# Outputs.net
KiCad netlist of a schematic drawn in Altium Designer
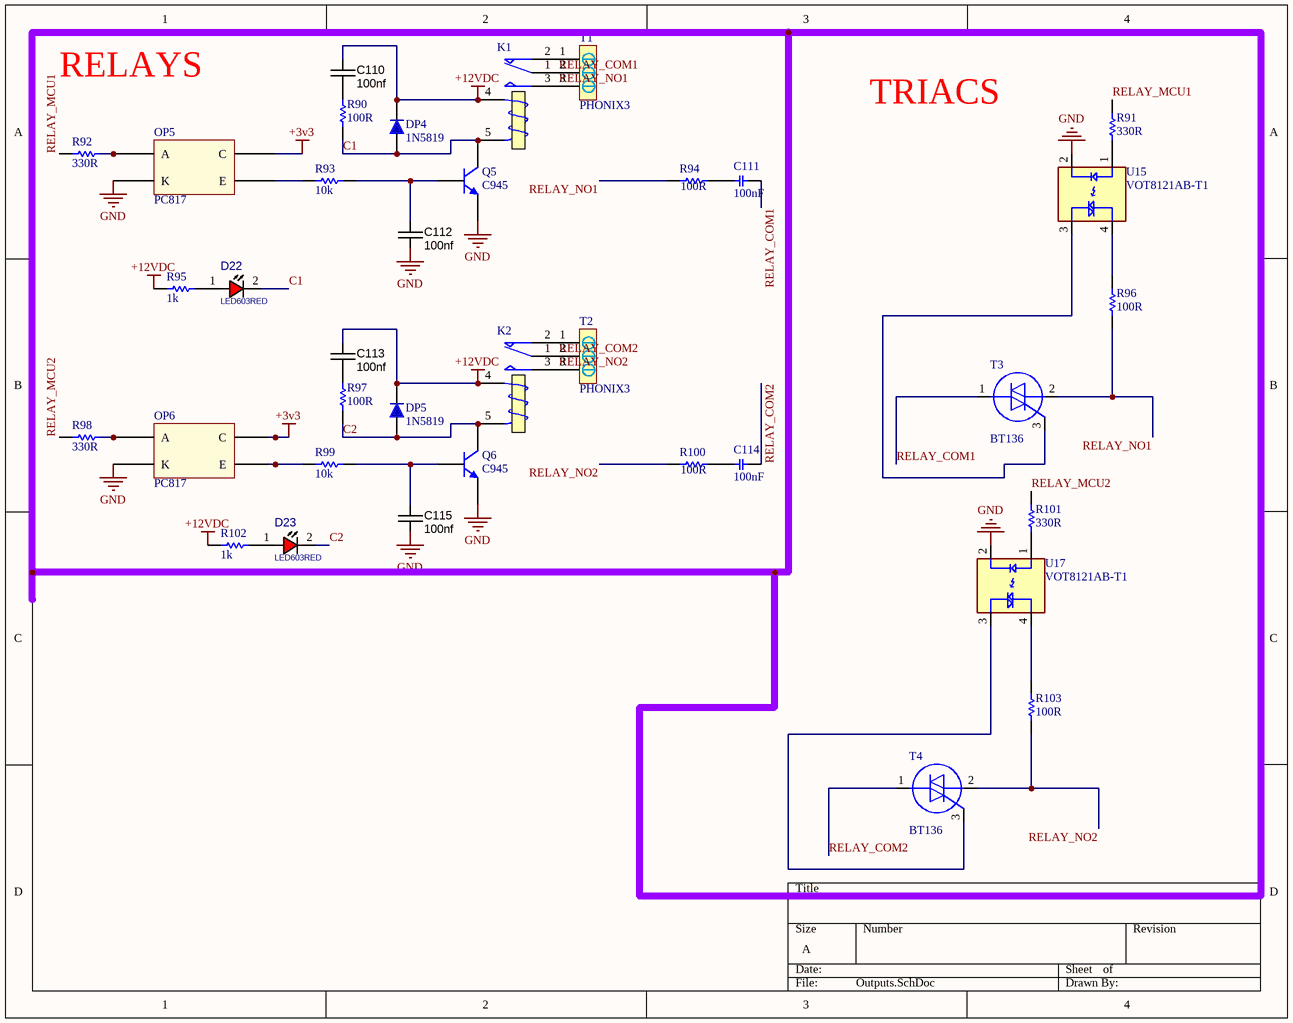
[diagram p0: Outputs.SchDoc]

(export (version "E")
  (design (tool "Eeschema 10.0.6"))
  (components
    (comp (ref "C110")
      (value "100nf")
      (footprint "CAPC1608X90N")
      (description "Capacitor SMD Cer 100nF 10% 50V X7R 0603")
      (fields (field (name "TOLERANCE") "±10%"))
      (libsource (lib "altium-import") (part "root_2_CAPC_100n_0603_X7R_50V_10%_"))
    )
    (comp (ref "C111")
      (value "100nF")
      (footprint "Cap - 10nF - 630V")
      (description "Capacitor Polyester THD")
      (libsource (lib "Capacitor") (part "Capacitor Polyester THD"))
    )
    (comp (ref "C112")
      (value "100nf")
      (footprint "CAPC1608X90N")
      (description "Capacitor SMD Cer 100nF 10% 50V X7R 0603")
      (fields (field (name "TOLERANCE") "±10%"))
      (libsource (lib "altium-import") (part "root_2_CAPC_100n_0603_X7R_50V_10%_"))
    )
    (comp (ref "C113")
      (value "100nf")
      (footprint "CAPC1608X90N")
      (description "Capacitor SMD Cer 100nF 10% 50V X7R 0603")
      (fields (field (name "TOLERANCE") "±10%"))
      (libsource (lib "altium-import") (part "root_2_CAPC_100n_0603_X7R_50V_10%_"))
    )
    (comp (ref "C114")
      (value "100nF")
      (footprint "Cap - 10nF - 630V")
      (description "Capacitor Polyester THD")
      (libsource (lib "Capacitor") (part "Capacitor Polyester THD"))
    )
    (comp (ref "C115")
      (value "100nf")
      (footprint "CAPC1608X90N")
      (description "Capacitor SMD Cer 100nF 10% 50V X7R 0603")
      (fields (field (name "TOLERANCE") "±10%"))
      (libsource (lib "altium-import") (part "root_2_CAPC_100n_0603_X7R_50V_10%_"))
    )
    (comp (ref "D22")
      (value "LED603RED")
      (footprint "LED0603RED")
      (description "LED, SMD, 0603, RED")
      (fields (field (name "MANF") "MANF") (field (name "MANF_P#") "MANF_PART#"))
      (libsource (lib "led(diode)") (part "LED_SMD_0603_RED"))
    )
    (comp (ref "D23")
      (value "LED603RED")
      (footprint "LED0603RED")
      (description "LED, SMD, 0603, RED")
      (fields (field (name "MANF") "MANF") (field (name "MANF_P#") "MANF_PART#"))
      (libsource (lib "led(diode)") (part "LED_SMD_0603_RED"))
    )
    (comp (ref "DP4")
      (value "1N5819")
      (footprint "430X270D")
      (description "Schottkey Rectifiers")
      (fields (field (name "DESIGNER") "Abbas Basereh"))
      (libsource (lib "2017AbbasBasereh9365731239 -ver1") (part "1N5819"))
    )
    (comp (ref "DP5")
      (value "1N5819")
      (footprint "430X270D")
      (description "Schottkey Rectifiers")
      (fields (field (name "DESIGNER") "Abbas Basereh"))
      (libsource (lib "2017AbbasBasereh9365731239 -ver1") (part "1N5819"))
    )
    (comp (ref "K1")
      (value "~")
      (footprint "Relay 18.85x15.35x15.70")
      (description "Single-Pole Dual-Throw Relay")
      (fields (field (name "DESIGNER") "Abbas Basereh"))
      (libsource (lib "altium-import") (part "root_0_Relay_SPDT_"))
    )
    (comp (ref "K2")
      (value "~")
      (footprint "Relay 18.85x15.35x15.70")
      (description "Single-Pole Dual-Throw Relay")
      (fields (field (name "DESIGNER") "Abbas Basereh"))
      (libsource (lib "altium-import") (part "root_0_Relay_SPDT_"))
    )
    (comp (ref "OP5")
      (value "PC817")
      (footprint "PC817 SMD")
      (description "PC817 optocpler")
      (libsource (lib "IC") (part "PC817"))
    )
    (comp (ref "OP6")
      (value "PC817")
      (footprint "PC817 SMD")
      (description "PC817 optocpler")
      (libsource (lib "IC") (part "PC817"))
    )
    (comp (ref "Q5")
      (value "C945")
      (footprint "SOT23_N")
      (description "NPN Silicon Epitaxial Planar Transistor")
      (fields (field (name "PUBLISHER") "Abbas Basereh"))
      (libsource (lib "altium-import") (part "root_0_C945_"))
    )
    (comp (ref "Q6")
      (value "C945")
      (footprint "SOT23_N")
      (description "NPN Silicon Epitaxial Planar Transistor")
      (fields (field (name "PUBLISHER") "Abbas Basereh"))
      (libsource (lib "altium-import") (part "root_0_C945_"))
    )
    (comp (ref "R90")
      (value "100R")
      (footprint "Resistor_SMD_0603 (1608)")
      (description "Resistor 0603")
      (fields (field (name "PUBLISHER") "Seyed Razi Vesali") (field (name "EMAIL") "razi.vesali@gmail.com"))
      (libsource (lib "resistors") (part "Resistor"))
    )
    (comp (ref "R91")
      (value "330R")
      (footprint "Resistor_SMD_0603 (1608)")
      (description "Resistor0603")
      (fields (field (name "PUBLISHER") "Seyed Razi Vesali") (field (name "EMAIL") "razi.vesali@gmail.com"))
      (libsource (lib "resistors") (part "Resistor"))
    )
    (comp (ref "R92")
      (value "330R")
      (footprint "Resistor_SMD_0603 (1608)")
      (description "Resistor")
      (fields (field (name "PUBLISHER") "Seyed Razi Vesali") (field (name "EMAIL") "razi.vesali@gmail.com"))
      (libsource (lib "resistors") (part "Resistor"))
    )
    (comp (ref "R93")
      (value "10k")
      (footprint "Resistor_SMD_0603 (1608)")
      (description "Resistor 0603")
      (fields (field (name "PUBLISHER") "Seyed Razi Vesali") (field (name "EMAIL") "razi.vesali@gmail.com"))
      (libsource (lib "resistors") (part "Resistor"))
    )
    (comp (ref "R94")
      (value "100R")
      (footprint "RES2512")
      (description "TOTAL SMD RESISTOR PACK 2512")
      (fields (field (name "DESIGNER") "Abbas Basereh"))
      (libsource (lib "altium-import") (part "root_2_RES SMD PACKAGE_"))
    )
    (comp (ref "R95")
      (value "1k")
      (footprint "Resistor_SMD_0603 (1608)")
      (description "Resistor")
      (fields (field (name "PUBLISHER") "Seyed Razi Vesali") (field (name "EMAIL") "razi.vesali@gmail.com"))
      (libsource (lib "resistors") (part "Resistor"))
    )
    (comp (ref "R96")
      (value "100R")
      (footprint "RES2512")
      (description "2512")
      (fields (field (name "DESIGNER") "Abbas Basereh"))
      (libsource (lib "altium-import") (part "root_1_RES SMD PACKAGE_"))
    )
    (comp (ref "R97")
      (value "100R")
      (footprint "Resistor_SMD_0603 (1608)")
      (description "Resistor")
      (fields (field (name "PUBLISHER") "Seyed Razi Vesali") (field (name "EMAIL") "razi.vesali@gmail.com"))
      (libsource (lib "resistors") (part "Resistor"))
    )
    (comp (ref "R98")
      (value "330R")
      (footprint "Resistor_SMD_0603 (1608)")
      (description "Resistor")
      (fields (field (name "PUBLISHER") "Seyed Razi Vesali") (field (name "EMAIL") "razi.vesali@gmail.com"))
      (libsource (lib "resistors") (part "Resistor"))
    )
    (comp (ref "R99")
      (value "10k")
      (footprint "Resistor_SMD_0603 (1608)")
      (description "Resistor")
      (fields (field (name "PUBLISHER") "Seyed Razi Vesali") (field (name "EMAIL") "razi.vesali@gmail.com"))
      (libsource (lib "resistors") (part "Resistor"))
    )
    (comp (ref "R100")
      (value "100R")
      (footprint "RES2512")
      (description "TOTAL SMD RESISTOR PACK 2512")
      (fields (field (name "DESIGNER") "Abbas Basereh"))
      (libsource (lib "altium-import") (part "root_2_RES SMD PACKAGE_"))
    )
    (comp (ref "R101")
      (value "330R")
      (footprint "Resistor_SMD_0603 (1608)")
      (description "Resistor0603")
      (fields (field (name "PUBLISHER") "Seyed Razi Vesali") (field (name "EMAIL") "razi.vesali@gmail.com"))
      (libsource (lib "resistors") (part "Resistor"))
    )
    (comp (ref "R102")
      (value "1k")
      (footprint "Resistor_SMD_0603 (1608)")
      (description "Resistor")
      (fields (field (name "PUBLISHER") "Seyed Razi Vesali") (field (name "EMAIL") "razi.vesali@gmail.com"))
      (libsource (lib "resistors") (part "Resistor"))
    )
    (comp (ref "R103")
      (value "100R")
      (footprint "RES2512")
      (description "2512")
      (fields (field (name "DESIGNER") "Abbas Basereh"))
      (libsource (lib "altium-import") (part "root_1_RES SMD PACKAGE_"))
    )
    (comp (ref "T1")
      (value "PHONIX3")
      (footprint "PHONIX3")
      (libsource (lib "altium-import") (part "root_3_mirrored_PHONIX3_"))
    )
    (comp (ref "T2")
      (value "PHONIX3")
      (footprint "PHONIX3")
      (libsource (lib "altium-import") (part "root_3_mirrored_PHONIX3_"))
    )
    (comp (ref "T3")
      (value "BT136")
      (footprint "TO252")
      (description "Triac")
      (fields
        (field (name "MANUFACTURER_PART_NUMBER") "BT136X-600E,127")
        (field (name "MOUSER PART NUMBER") "771-BT136X-600E127")
      )
      (libsource (lib "*") (part "BT136X-600E,127"))
    )
    (comp (ref "T4")
      (value "BT136")
      (footprint "TO252")
      (description "Triac")
      (fields
        (field (name "MANUFACTURER_PART_NUMBER") "BT136X-600E,127")
        (field (name "MOUSER PART NUMBER") "771-BT136X-600E127")
      )
      (libsource (lib "*") (part "BT136X-600E,127"))
    )
    (comp (ref "U15")
      (value "VOT8121AB-T1")
      (footprint "SOIC254P1016X440-4N")
      (description "Optoisolator Triac Output 5300Vrms 1 Channel 4-SMD")
      (fields (field (name "MF") "Vishay Semiconductor Opto Division"))
      (libsource (lib "altium-import") (part "root_3_VOT8121AB-T1_"))
    )
    (comp (ref "U17")
      (value "VOT8121AB-T1")
      (footprint "SOIC254P1016X440-4N")
      (description "Optoisolator Triac Output 5300Vrms 1 Channel 4-SMD")
      (fields (field (name "MF") "Vishay Semiconductor Opto Division"))
      (libsource (lib "altium-import") (part "root_3_VOT8121AB-T1_"))
    )
  )
  (nets
    (net (code "1") (name "+3v3") (class "Default")
      (node (ref "OP5") (pin "4") (pinfunction "C_4") (pintype "passive"))
      (node (ref "OP6") (pin "4") (pinfunction "C_4") (pintype "passive"))
    )
    (net (code "2") (name "+12VDC") (class "Default")
      (node (ref "C110") (pin "2") (pintype "passive"))
      (node (ref "C113") (pin "2") (pintype "passive"))
      (node (ref "DP4") (pin "2") (pintype "passive"))
      (node (ref "DP5") (pin "2") (pintype "passive"))
      (node (ref "K1") (pin "4") (pinfunction "T1_4") (pintype "passive"))
      (node (ref "K2") (pin "4") (pinfunction "T1_4") (pintype "passive"))
      (node (ref "R102") (pin "1") (pinfunction "1_1") (pintype "passive"))
      (node (ref "R95") (pin "1") (pinfunction "1_1") (pintype "passive"))
    )
    (net (code "3") (name "/C1") (class "Default")
      (node (ref "D22") (pin "2") (pinfunction "CATHODE_2") (pintype "passive"))
      (node (ref "DP4") (pin "1") (pintype "passive"))
      (node (ref "K1") (pin "5") (pinfunction "T2_5") (pintype "passive"))
      (node (ref "Q5") (pin "3") (pinfunction "C_3") (pintype "passive"))
      (node (ref "R90") (pin "2") (pinfunction "2_2") (pintype "passive"))
    )
    (net (code "4") (name "/C2") (class "Default")
      (node (ref "D23") (pin "2") (pinfunction "CATHODE_2") (pintype "passive"))
      (node (ref "DP5") (pin "1") (pintype "passive"))
      (node (ref "K2") (pin "5") (pinfunction "T2_5") (pintype "passive"))
      (node (ref "Q6") (pin "3") (pinfunction "C_3") (pintype "passive"))
      (node (ref "R97") (pin "2") (pinfunction "2_2") (pintype "passive"))
    )
    (net (code "5") (name "/RELAY_COM1") (class "Default")
      (node (ref "C111") (pin "1") (pinfunction "1_1") (pintype "passive"))
      (node (ref "K1") (pin "1") (pinfunction "COM_1") (pintype "passive"))
      (node (ref "T1") (pin "2") (pintype "passive"))
      (node (ref "T3") (pin "1") (pinfunction "MT1_1") (pintype "passive"))
    )
    (net (code "6") (name "/RELAY_COM2") (class "Default")
      (node (ref "C114") (pin "1") (pinfunction "1_1") (pintype "passive"))
      (node (ref "K2") (pin "1") (pinfunction "COM_1") (pintype "passive"))
      (node (ref "T2") (pin "2") (pintype "passive"))
      (node (ref "T4") (pin "1") (pinfunction "MT1_1") (pintype "passive"))
    )
    (net (code "7") (name "/RELAY_MCU1") (class "Default")
      (node (ref "R91") (pin "1") (pinfunction "1_1") (pintype "passive"))
      (node (ref "R92") (pin "1") (pinfunction "1_1") (pintype "passive"))
    )
    (net (code "8") (name "/RELAY_MCU2") (class "Default")
      (node (ref "R101") (pin "1") (pinfunction "1_1") (pintype "passive"))
      (node (ref "R98") (pin "1") (pinfunction "1_1") (pintype "passive"))
    )
    (net (code "9") (name "/RELAY_NO1") (class "Default")
      (node (ref "K1") (pin "3") (pinfunction "NO_3") (pintype "passive"))
      (node (ref "R94") (pin "2") (pinfunction "2_2") (pintype "passive"))
      (node (ref "R96") (pin "1") (pinfunction "1_1") (pintype "passive"))
      (node (ref "T1") (pin "3") (pintype "passive"))
      (node (ref "T3") (pin "2") (pinfunction "MT2_2") (pintype "passive"))
    )
    (net (code "10") (name "/RELAY_NO2") (class "Default")
      (node (ref "K2") (pin "3") (pinfunction "NO_3") (pintype "passive"))
      (node (ref "R100") (pin "2") (pinfunction "2_2") (pintype "passive"))
      (node (ref "R103") (pin "1") (pinfunction "1_1") (pintype "passive"))
      (node (ref "T2") (pin "3") (pintype "passive"))
      (node (ref "T4") (pin "2") (pinfunction "MT2_2") (pintype "passive"))
    )
    (net (code "11") (name "GND") (class "Default")
      (node (ref "C112") (pin "1") (pintype "passive"))
      (node (ref "C115") (pin "1") (pintype "passive"))
      (node (ref "OP5") (pin "2") (pinfunction "K_2") (pintype "passive"))
      (node (ref "OP6") (pin "2") (pinfunction "K_2") (pintype "passive"))
      (node (ref "Q5") (pin "2") (pinfunction "E_2") (pintype "passive"))
      (node (ref "Q6") (pin "2") (pinfunction "E_2") (pintype "passive"))
      (node (ref "U15") (pin "2") (pinfunction "C_2") (pintype "passive"))
      (node (ref "U17") (pin "2") (pinfunction "C_2") (pintype "passive"))
    )
    (net (code "12") (name "Net-(C110-Pad1)") (class "Default")
      (node (ref "C110") (pin "1") (pintype "passive"))
      (node (ref "R90") (pin "1") (pinfunction "1_1") (pintype "passive"))
    )
    (net (code "13") (name "Net-(C111-Pad2)") (class "Default")
      (node (ref "C111") (pin "2") (pinfunction "2_2") (pintype "passive"))
      (node (ref "R94") (pin "1") (pinfunction "1_1") (pintype "passive"))
    )
    (net (code "14") (name "Net-(C113-Pad1)") (class "Default")
      (node (ref "C113") (pin "1") (pintype "passive"))
      (node (ref "R97") (pin "1") (pinfunction "1_1") (pintype "passive"))
    )
    (net (code "15") (name "Net-(C114-Pad2)") (class "Default")
      (node (ref "C114") (pin "2") (pinfunction "2_2") (pintype "passive"))
      (node (ref "R100") (pin "1") (pinfunction "1_1") (pintype "passive"))
    )
    (net (code "16") (name "Net-(D22-ANODE)") (class "Default")
      (node (ref "D22") (pin "1") (pinfunction "ANODE_1") (pintype "passive"))
      (node (ref "R95") (pin "2") (pinfunction "2_2") (pintype "passive"))
    )
    (net (code "17") (name "Net-(D23-ANODE)") (class "Default")
      (node (ref "D23") (pin "1") (pinfunction "ANODE_1") (pintype "passive"))
      (node (ref "R102") (pin "2") (pinfunction "2_2") (pintype "passive"))
    )
    (net (code "18") (name "Net-(K1-NC)") (class "Default")
      (node (ref "K1") (pin "2") (pinfunction "NC_2") (pintype "passive"))
      (node (ref "T1") (pin "1") (pintype "passive"))
    )
    (net (code "19") (name "Net-(K2-NC)") (class "Default")
      (node (ref "K2") (pin "2") (pinfunction "NC_2") (pintype "passive"))
      (node (ref "T2") (pin "1") (pintype "passive"))
    )
    (net (code "20") (name "Net-(OP5-A)") (class "Default")
      (node (ref "OP5") (pin "1") (pinfunction "A_1") (pintype "passive"))
      (node (ref "R92") (pin "2") (pinfunction "2_2") (pintype "passive"))
    )
    (net (code "21") (name "Net-(OP5-E)") (class "Default")
      (node (ref "OP5") (pin "3") (pinfunction "E_3") (pintype "passive"))
      (node (ref "R93") (pin "1") (pinfunction "1_1") (pintype "passive"))
    )
    (net (code "22") (name "Net-(OP6-A)") (class "Default")
      (node (ref "OP6") (pin "1") (pinfunction "A_1") (pintype "passive"))
      (node (ref "R98") (pin "2") (pinfunction "2_2") (pintype "passive"))
    )
    (net (code "23") (name "Net-(OP6-E)") (class "Default")
      (node (ref "OP6") (pin "3") (pinfunction "E_3") (pintype "passive"))
      (node (ref "R99") (pin "1") (pinfunction "1_1") (pintype "passive"))
    )
    (net (code "24") (name "Net-(Q5-B)") (class "Default")
      (node (ref "C112") (pin "2") (pintype "passive"))
      (node (ref "Q5") (pin "1") (pinfunction "B_1") (pintype "passive"))
      (node (ref "R93") (pin "2") (pinfunction "2_2") (pintype "passive"))
    )
    (net (code "25") (name "Net-(Q6-B)") (class "Default")
      (node (ref "C115") (pin "2") (pintype "passive"))
      (node (ref "Q6") (pin "1") (pinfunction "B_1") (pintype "passive"))
      (node (ref "R99") (pin "2") (pinfunction "2_2") (pintype "passive"))
    )
    (net (code "26") (name "Net-(T3-G)") (class "Default")
      (node (ref "T3") (pin "3") (pinfunction "G_3") (pintype "passive"))
      (node (ref "U15") (pin "3") (pinfunction "MT1_3") (pintype "passive"))
    )
    (net (code "27") (name "Net-(T4-G)") (class "Default")
      (node (ref "T4") (pin "3") (pinfunction "G_3") (pintype "passive"))
      (node (ref "U17") (pin "3") (pinfunction "MT1_3") (pintype "passive"))
    )
    (net (code "28") (name "Net-(U15-A)") (class "Default")
      (node (ref "R91") (pin "2") (pinfunction "2_2") (pintype "passive"))
      (node (ref "U15") (pin "1") (pinfunction "A_1") (pintype "passive"))
    )
    (net (code "29") (name "Net-(U15-MT2)") (class "Default")
      (node (ref "R96") (pin "2") (pinfunction "2_2") (pintype "passive"))
      (node (ref "U15") (pin "4") (pinfunction "MT2_4") (pintype "passive"))
    )
    (net (code "30") (name "Net-(U17-A)") (class "Default")
      (node (ref "R101") (pin "2") (pinfunction "2_2") (pintype "passive"))
      (node (ref "U17") (pin "1") (pinfunction "A_1") (pintype "passive"))
    )
    (net (code "31") (name "Net-(U17-MT2)") (class "Default")
      (node (ref "R103") (pin "2") (pinfunction "2_2") (pintype "passive"))
      (node (ref "U17") (pin "4") (pinfunction "MT2_4") (pintype "passive"))
    )
  )
)
